# Detection_Circuit.net
KiCad netlist of a schematic drawn in Altium Designer
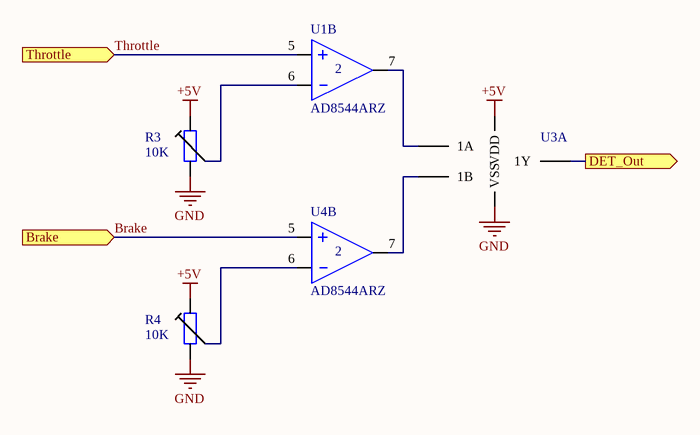
[diagram p0: Detection Circuit.SchDoc]

(export (version "E")
  (design (tool "Eeschema 10.0.6"))
  (components
    (comp (ref "R3")
      (value "10K")
      (footprint "RESDFN3_475X200X100L160X130N")
      (fields
        (field (name "PART NUMBER") "Trimmer_10K_0W250")
        (field (name "MANUFACTURER PART NUMBER") "PVG5A103C03B00")
      )
      (libsource (lib "FR") (part "Trimmer"))
    )
    (comp (ref "R4")
      (value "10K")
      (footprint "RESDFN3_475X200X100L160X130N")
      (fields
        (field (name "PART NUMBER") "Trimmer_10K_0W250")
        (field (name "MANUFACTURER PART NUMBER") "PVG5A103C03B00")
      )
      (libsource (lib "FR") (part "Trimmer"))
    )
    (comp (ref "U1")
      (value "AD8544ARZ")
      (footprint "SOIC14P127_865X600X175L83X41N")
      (fields
        (field (name "PART NUMBER") "AD8544")
        (field (name "MANUFACTURER PART NUMBER") "AD8544ARZ-REEL")
      )
      (libsource (lib "FR") (part "AD8544"))
    )
    (comp (ref "U3")
      (value "HEF4081BT")
      (footprint "SOIC14P127_865X600X175L70X42N")
      (fields (field (name "MANUFACTURER PART NUMBER") "HEF4081BT,653"))
      (libsource (lib "FR") (part "HEF4081BT"))
    )
    (comp (ref "U4")
      (value "AD8544ARZ")
      (footprint "SOIC14P127_865X600X175L83X41N")
      (fields
        (field (name "PART NUMBER") "AD8544")
        (field (name "MANUFACTURER PART NUMBER") "AD8544ARZ-REEL")
      )
      (libsource (lib "FR") (part "AD8544"))
    )
  )
  (nets
    (net (code "1") (name "+5V") (class "Default")
      (node (ref "R3") (pin "3") (pinfunction "3_3") (pintype "passive"))
      (node (ref "R4") (pin "3") (pinfunction "3_3") (pintype "passive"))
      (node (ref "U3") (pin "14") (pinfunction "VDD_14") (pintype "power_in"))
    )
    (net (code "2") (name "/Brake") (class "Default") (node (ref "U4") (pin "5") (pintype "passive")))
    (net (code "3") (name "/DET_Out") (class "Default")
      (node (ref "U3") (pin "3") (pinfunction "1Y_3") (pintype "passive"))
    )
    (net (code "4") (name "/Throttle") (class "Default") (node (ref "U1") (pin "5") (pintype "passive")))
    (net (code "5") (name "GND") (class "Default")
      (node (ref "R3") (pin "1") (pinfunction "1_1") (pintype "passive"))
      (node (ref "R4") (pin "1") (pinfunction "1_1") (pintype "passive"))
      (node (ref "U3") (pin "7") (pinfunction "VSS_7") (pintype "passive"))
    )
    (net (code "6") (name "Net-(R3-Pad2)") (class "Default")
      (node (ref "R3") (pin "2") (pinfunction "2_2") (pintype "passive"))
      (node (ref "U1") (pin "6") (pintype "passive"))
    )
    (net (code "7") (name "Net-(R4-Pad2)") (class "Default")
      (node (ref "R4") (pin "2") (pinfunction "2_2") (pintype "passive"))
      (node (ref "U4") (pin "6") (pintype "passive"))
    )
    (net (code "8") (name "Net-(U3A-1A)") (class "Default")
      (node (ref "U1") (pin "7") (pintype "passive"))
      (node (ref "U3") (pin "1") (pinfunction "1A_1") (pintype "passive"))
    )
    (net (code "9") (name "Net-(U3A-1B)") (class "Default")
      (node (ref "U3") (pin "2") (pinfunction "1B_2") (pintype "passive"))
      (node (ref "U4") (pin "7") (pintype "passive"))
    )
  )
)
